# driver_ANNOTATED.net
KiCad netlist of a schematic drawn in EAGLE
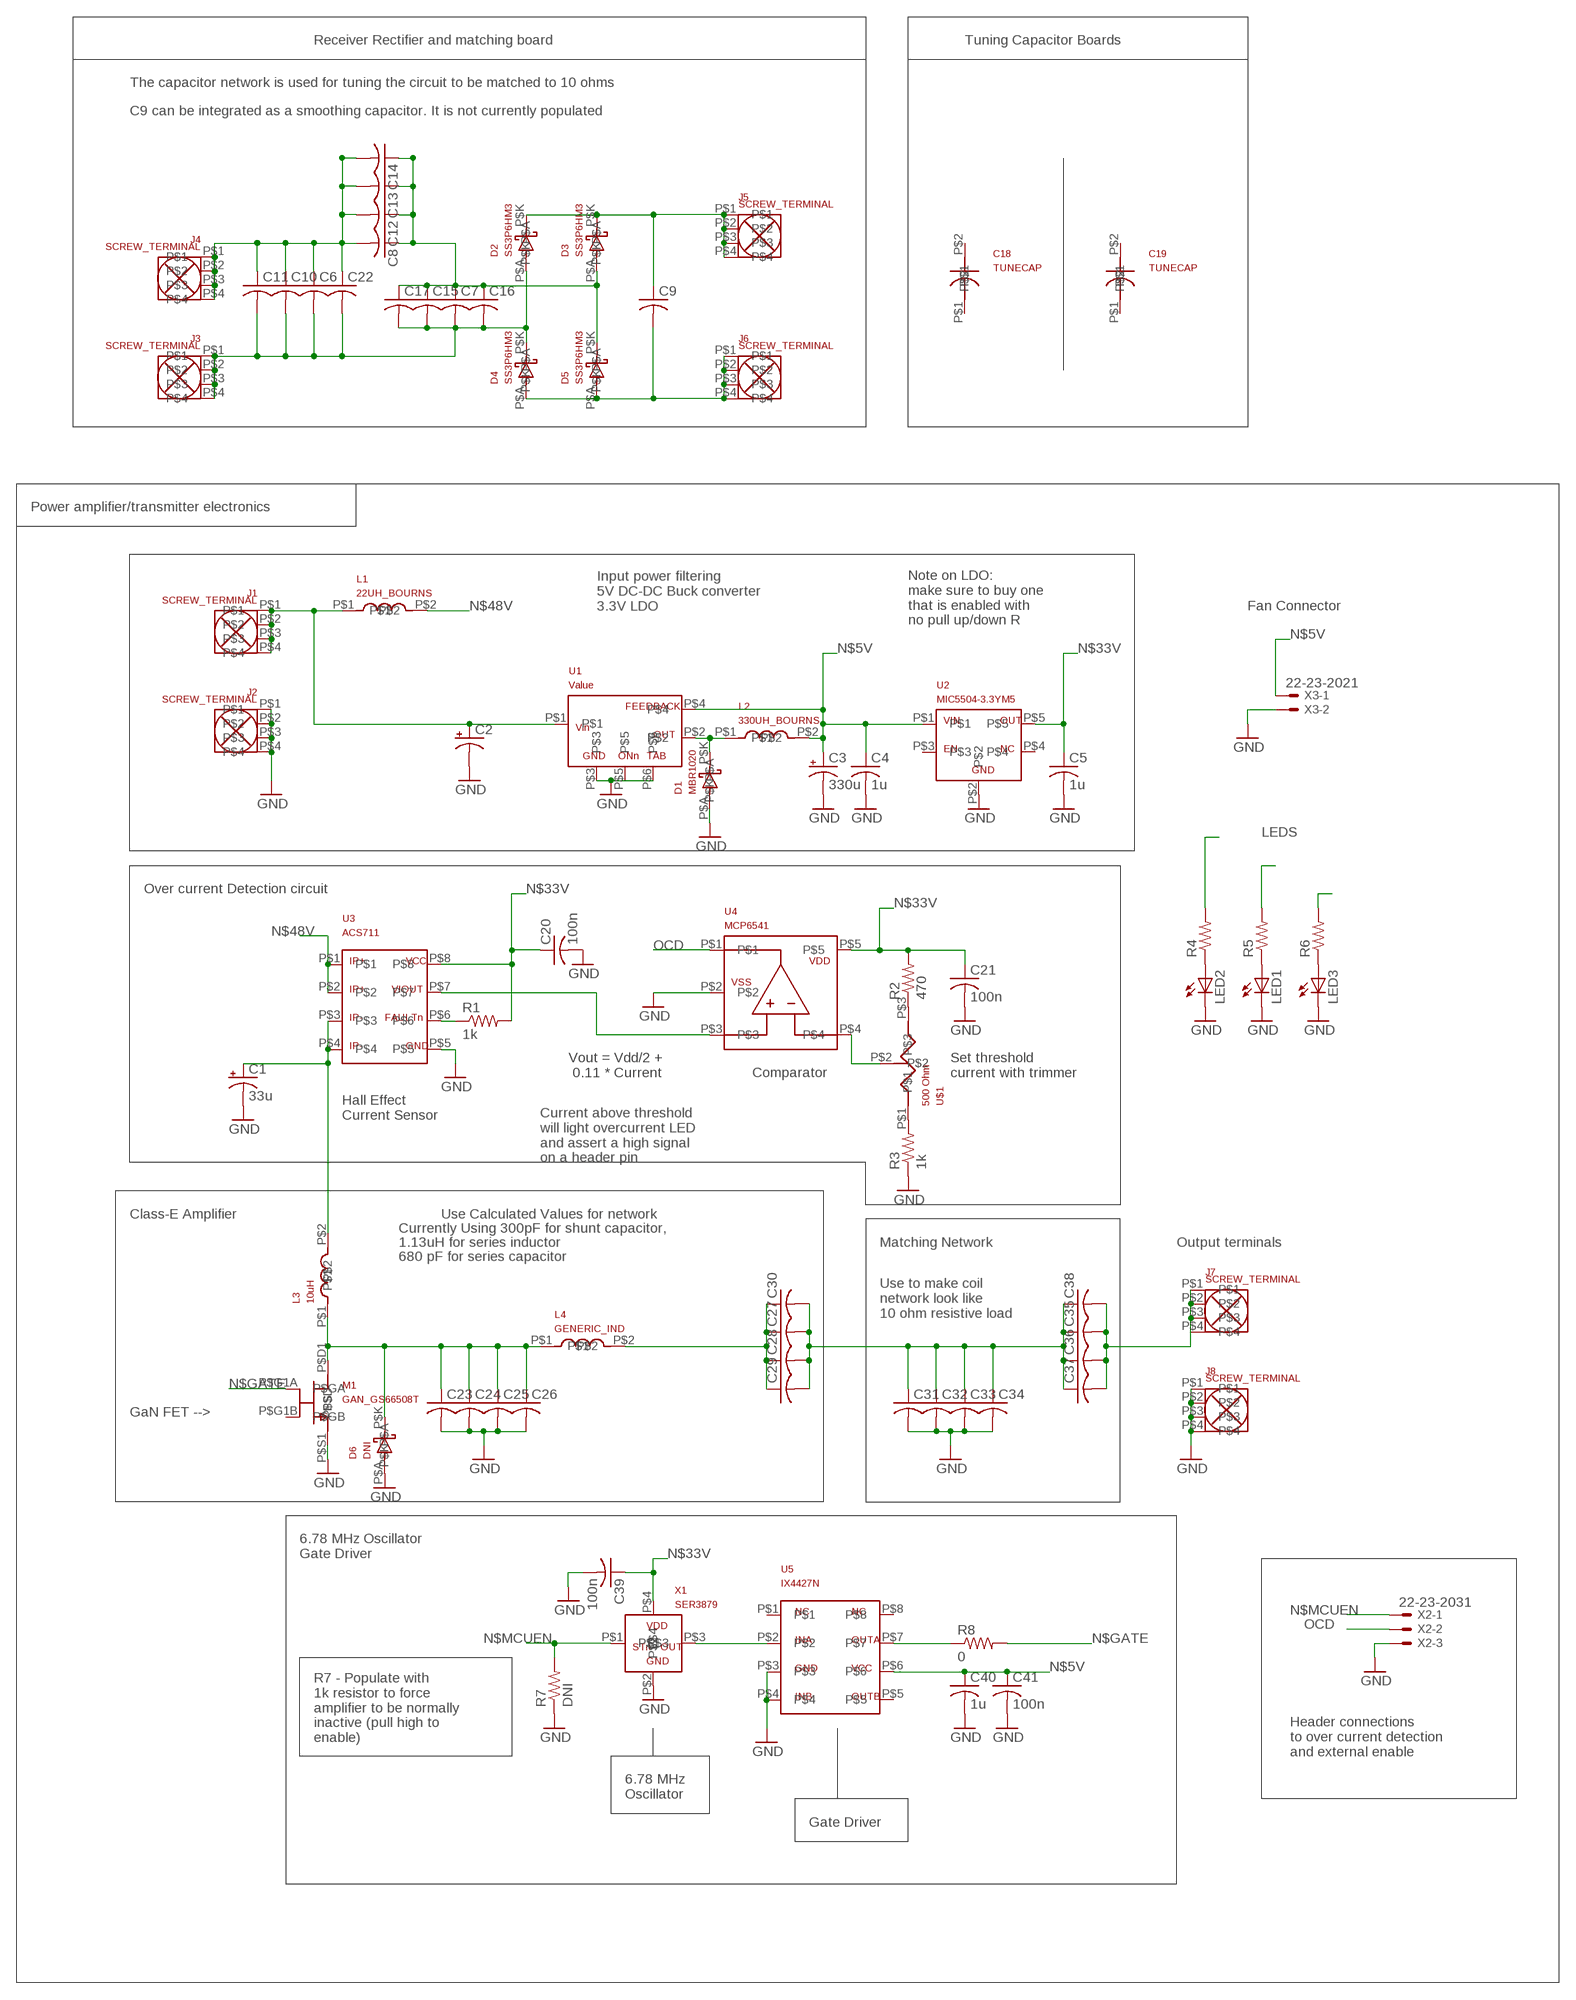
[diagram p0: schematic, sheet 1]

(export (version "E")
  (design (tool "Eeschema 10.0.6"))
  (components
    (comp (ref "C1")
      (value "33u")
      (footprint "eagle-import:140CLH-0810")
      (libsource (lib "eagle-import") (part "CPOL-US140CLH-0810"))
    )
    (comp (ref "C2")
      (value "CPOL-US140CLH-1010")
      (footprint "eagle-import:140CLH-1010")
      (libsource (lib "eagle-import") (part "CPOL-US140CLH-1010"))
    )
    (comp (ref "C3")
      (value "330u")
      (footprint "eagle-import:150CLZ-0810")
      (libsource (lib "eagle-import") (part "CPOL-US150CLZ-0810"))
    )
    (comp (ref "C4")
      (value "1u")
      (footprint "eagle-import:C0603K")
      (libsource (lib "eagle-import") (part "C-USC0603K"))
    )
    (comp (ref "C5")
      (value "1u")
      (footprint "eagle-import:C0603K")
      (libsource (lib "eagle-import") (part "C-USC0603K"))
    )
    (comp (ref "C6")
      (value "C-USC1206K")
      (footprint "eagle-import:C1206K")
      (libsource (lib "eagle-import") (part "C-USC1206K"))
    )
    (comp (ref "C7")
      (value "C-USC1206K")
      (footprint "eagle-import:C1206K")
      (libsource (lib "eagle-import") (part "C-USC1206K"))
    )
    (comp (ref "C8")
      (value "C-USC1206K")
      (footprint "eagle-import:C1206K")
      (libsource (lib "eagle-import") (part "C-USC1206K"))
    )
    (comp (ref "C9")
      (value "C-USC1206K")
      (footprint "eagle-import:C1206K")
      (libsource (lib "eagle-import") (part "C-USC1206K"))
    )
    (comp (ref "C10")
      (value "C-USC1206K")
      (footprint "eagle-import:C1206K")
      (libsource (lib "eagle-import") (part "C-USC1206K"))
    )
    (comp (ref "C11")
      (value "C-USC1206K")
      (footprint "eagle-import:C1206K")
      (libsource (lib "eagle-import") (part "C-USC1206K"))
    )
    (comp (ref "C12")
      (value "C-USC1206K")
      (footprint "eagle-import:C1206K")
      (libsource (lib "eagle-import") (part "C-USC1206K"))
    )
    (comp (ref "C13")
      (value "C-USC1206K")
      (footprint "eagle-import:C1206K")
      (libsource (lib "eagle-import") (part "C-USC1206K"))
    )
    (comp (ref "C14")
      (value "C-USC1206K")
      (footprint "eagle-import:C1206K")
      (libsource (lib "eagle-import") (part "C-USC1206K"))
    )
    (comp (ref "C15")
      (value "C-USC1206K")
      (footprint "eagle-import:C1206K")
      (libsource (lib "eagle-import") (part "C-USC1206K"))
    )
    (comp (ref "C16")
      (value "C-USC1206K")
      (footprint "eagle-import:C1206K")
      (libsource (lib "eagle-import") (part "C-USC1206K"))
    )
    (comp (ref "C17")
      (value "C-USC1206K")
      (footprint "eagle-import:C1206K")
      (libsource (lib "eagle-import") (part "C-USC1206K"))
    )
    (comp (ref "C18")
      (value "TUNECAP")
      (footprint "eagle-import:CAPTUNE")
      (libsource (lib "eagle-import") (part "TUNECAP"))
    )
    (comp (ref "C19")
      (value "TUNECAP")
      (footprint "eagle-import:CAPTUNE")
      (libsource (lib "eagle-import") (part "TUNECAP"))
    )
    (comp (ref "C20")
      (value "100n")
      (footprint "eagle-import:C0603")
      (libsource (lib "eagle-import") (part "C-USC0603"))
    )
    (comp (ref "C21")
      (value "100n")
      (footprint "eagle-import:C0603K")
      (libsource (lib "eagle-import") (part "C-USC0603K"))
    )
    (comp (ref "C22")
      (value "C-USC1206K")
      (footprint "eagle-import:C1206K")
      (libsource (lib "eagle-import") (part "C-USC1206K"))
    )
    (comp (ref "C23")
      (value "C-USC1206K")
      (footprint "eagle-import:C1206K")
      (libsource (lib "eagle-import") (part "C-USC1206K"))
    )
    (comp (ref "C24")
      (value "C-USC1206K")
      (footprint "eagle-import:C1206K")
      (libsource (lib "eagle-import") (part "C-USC1206K"))
    )
    (comp (ref "C25")
      (value "C-USC1206K")
      (footprint "eagle-import:C1206K")
      (libsource (lib "eagle-import") (part "C-USC1206K"))
    )
    (comp (ref "C26")
      (value "C-USC1206K")
      (footprint "eagle-import:C1206K")
      (libsource (lib "eagle-import") (part "C-USC1206K"))
    )
    (comp (ref "C27")
      (value "C-USC1206K")
      (footprint "eagle-import:C1206K")
      (libsource (lib "eagle-import") (part "C-USC1206K"))
    )
    (comp (ref "C28")
      (value "C-USC1206K")
      (footprint "eagle-import:C1206K")
      (libsource (lib "eagle-import") (part "C-USC1206K"))
    )
    (comp (ref "C29")
      (value "C-USC1206K")
      (footprint "eagle-import:C1206K")
      (libsource (lib "eagle-import") (part "C-USC1206K"))
    )
    (comp (ref "C30")
      (value "C-USC1206K")
      (footprint "eagle-import:C1206K")
      (libsource (lib "eagle-import") (part "C-USC1206K"))
    )
    (comp (ref "C31")
      (value "C-USC1206K")
      (footprint "eagle-import:C1206K")
      (libsource (lib "eagle-import") (part "C-USC1206K"))
    )
    (comp (ref "C32")
      (value "C-USC1206K")
      (footprint "eagle-import:C1206K")
      (libsource (lib "eagle-import") (part "C-USC1206K"))
    )
    (comp (ref "C33")
      (value "C-USC1206K")
      (footprint "eagle-import:C1206K")
      (libsource (lib "eagle-import") (part "C-USC1206K"))
    )
    (comp (ref "C34")
      (value "C-USC1206K")
      (footprint "eagle-import:C1206K")
      (libsource (lib "eagle-import") (part "C-USC1206K"))
    )
    (comp (ref "C35")
      (value "C-USC1206K")
      (footprint "eagle-import:C1206K")
      (libsource (lib "eagle-import") (part "C-USC1206K"))
    )
    (comp (ref "C36")
      (value "C-USC1206K")
      (footprint "eagle-import:C1206K")
      (libsource (lib "eagle-import") (part "C-USC1206K"))
    )
    (comp (ref "C37")
      (value "C-USC1206K")
      (footprint "eagle-import:C1206K")
      (libsource (lib "eagle-import") (part "C-USC1206K"))
    )
    (comp (ref "C38")
      (value "C-USC1206K")
      (footprint "eagle-import:C1206K")
      (libsource (lib "eagle-import") (part "C-USC1206K"))
    )
    (comp (ref "C39")
      (value "100n")
      (footprint "eagle-import:C0603K")
      (libsource (lib "eagle-import") (part "C-USC0603K"))
    )
    (comp (ref "C40")
      (value "1u")
      (footprint "eagle-import:C0603K")
      (libsource (lib "eagle-import") (part "C-USC0603K"))
    )
    (comp (ref "C41")
      (value "100n")
      (footprint "eagle-import:C0603K")
      (libsource (lib "eagle-import") (part "C-USC0603K"))
    )
    (comp (ref "D1")
      (value "MBR1020")
      (footprint "eagle-import:SOD-123")
      (libsource (lib "eagle-import") (part "MBR1020"))
    )
    (comp (ref "D2")
      (value "SS3P6HM3")
      (footprint "eagle-import:D0-220")
      (libsource (lib "eagle-import") (part "SS3P6HM3"))
    )
    (comp (ref "D3")
      (value "SS3P6HM3")
      (footprint "eagle-import:D0-220")
      (libsource (lib "eagle-import") (part "SS3P6HM3"))
    )
    (comp (ref "D4")
      (value "SS3P6HM3")
      (footprint "eagle-import:D0-220")
      (libsource (lib "eagle-import") (part "SS3P6HM3"))
    )
    (comp (ref "D5")
      (value "SS3P6HM3")
      (footprint "eagle-import:D0-220")
      (libsource (lib "eagle-import") (part "SS3P6HM3"))
    )
    (comp (ref "D6")
      (value "DNI")
      (footprint "eagle-import:D0-220")
      (libsource (lib "eagle-import") (part "SS3P6HM3"))
    )
    (comp (ref "J1")
      (value "SCREW_TERMINAL")
      (footprint "eagle-import:SCREW_TERMINAL")
      (libsource (lib "eagle-import") (part "SCREW_TERMINAL"))
    )
    (comp (ref "J2")
      (value "SCREW_TERMINAL")
      (footprint "eagle-import:SCREW_TERMINAL")
      (libsource (lib "eagle-import") (part "SCREW_TERMINAL"))
    )
    (comp (ref "J3")
      (value "SCREW_TERMINAL")
      (footprint "eagle-import:SCREW_TERMINAL")
      (libsource (lib "eagle-import") (part "SCREW_TERMINAL"))
    )
    (comp (ref "J4")
      (value "SCREW_TERMINAL")
      (footprint "eagle-import:SCREW_TERMINAL")
      (libsource (lib "eagle-import") (part "SCREW_TERMINAL"))
    )
    (comp (ref "J5")
      (value "SCREW_TERMINAL")
      (footprint "eagle-import:SCREW_TERMINAL")
      (libsource (lib "eagle-import") (part "SCREW_TERMINAL"))
    )
    (comp (ref "J6")
      (value "SCREW_TERMINAL")
      (footprint "eagle-import:SCREW_TERMINAL")
      (libsource (lib "eagle-import") (part "SCREW_TERMINAL"))
    )
    (comp (ref "J7")
      (value "SCREW_TERMINAL")
      (footprint "eagle-import:SCREW_TERMINAL")
      (libsource (lib "eagle-import") (part "SCREW_TERMINAL"))
    )
    (comp (ref "J8")
      (value "SCREW_TERMINAL")
      (footprint "eagle-import:SCREW_TERMINAL")
      (libsource (lib "eagle-import") (part "SCREW_TERMINAL"))
    )
    (comp (ref "L1")
      (value "22UH_BOURNS")
      (footprint "eagle-import:492MIL_IND")
      (libsource (lib "eagle-import") (part "22UH_BOURNS"))
    )
    (comp (ref "L2")
      (value "330UH_BOURNS")
      (footprint "eagle-import:330U_IND")
      (libsource (lib "eagle-import") (part "330UH_BOURNS"))
    )
    (comp (ref "L3")
      (value "10uH")
      (footprint "eagle-import:GENERIC_IND")
      (libsource (lib "eagle-import") (part "GENERIC_IND"))
    )
    (comp (ref "L4")
      (value "GENERIC_IND")
      (footprint "eagle-import:GENERIC_IND")
      (libsource (lib "eagle-import") (part "GENERIC_IND"))
    )
    (comp (ref "LED1")
      (value "LEDCHIPLED_0805")
      (footprint "eagle-import:CHIPLED_0805")
      (libsource (lib "eagle-import") (part "LEDCHIPLED_0805"))
    )
    (comp (ref "LED2")
      (value "LEDCHIPLED_0805")
      (footprint "eagle-import:CHIPLED_0805")
      (libsource (lib "eagle-import") (part "LEDCHIPLED_0805"))
    )
    (comp (ref "LED3")
      (value "LEDCHIPLED_0805")
      (footprint "eagle-import:CHIPLED_0805")
      (libsource (lib "eagle-import") (part "LEDCHIPLED_0805"))
    )
    (comp (ref "M1")
      (value "GAN_GS66508T")
      (footprint "eagle-import:GAN_GS66508T")
      (libsource (lib "eagle-import") (part "GAN_GS66508T"))
    )
    (comp (ref "R1")
      (value "1k")
      (footprint "eagle-import:R0603")
      (libsource (lib "eagle-import") (part "R-US_R0603"))
    )
    (comp (ref "R2")
      (value "470")
      (footprint "eagle-import:R0603")
      (libsource (lib "eagle-import") (part "R-US_R0603"))
    )
    (comp (ref "R3")
      (value "1k")
      (footprint "eagle-import:R0603")
      (libsource (lib "eagle-import") (part "R-US_R0603"))
    )
    (comp (ref "R4")
      (value "R-US_R0603")
      (footprint "eagle-import:R0603")
      (libsource (lib "eagle-import") (part "R-US_R0603"))
    )
    (comp (ref "R5")
      (value "R-US_R0603")
      (footprint "eagle-import:R0603")
      (libsource (lib "eagle-import") (part "R-US_R0603"))
    )
    (comp (ref "R6")
      (value "R-US_R0603")
      (footprint "eagle-import:R0603")
      (libsource (lib "eagle-import") (part "R-US_R0603"))
    )
    (comp (ref "R7")
      (value "DNI")
      (footprint "eagle-import:R0603")
      (libsource (lib "eagle-import") (part "R-US_R0603"))
    )
    (comp (ref "R8")
      (value "0")
      (footprint "eagle-import:R0603")
      (libsource (lib "eagle-import") (part "R-US_R0603"))
    )
    (comp (ref "U$1")
      (value "500 Ohm")
      (footprint "eagle-import:TRIMMER")
      (libsource (lib "eagle-import") (part "TRIMMER"))
    )
    (comp (ref "U1")
      (value "TL2575HV")
      (footprint "eagle-import:TL2575HV")
      (libsource (lib "eagle-import") (part "TL2575HV"))
    )
    (comp (ref "U2")
      (value "MIC5504-3.3YM5")
      (footprint "eagle-import:MIC5504-3.3YM5")
      (libsource (lib "eagle-import") (part "MIC5504-3.3YM5"))
    )
    (comp (ref "U3")
      (value "ACS711")
      (footprint "eagle-import:IX4427N")
      (libsource (lib "eagle-import") (part "ACS711"))
    )
    (comp (ref "U4")
      (value "MCP6541")
      (footprint "eagle-import:SC-70-5")
      (libsource (lib "eagle-import") (part "MCP6541"))
    )
    (comp (ref "U5")
      (value "IX4427N")
      (footprint "eagle-import:IX4427N")
      (libsource (lib "eagle-import") (part "IX4427N"))
    )
    (comp (ref "X1")
      (value "SER3879")
      (footprint "eagle-import:SER3879-ND")
      (libsource (lib "eagle-import") (part "SER3879"))
    )
    (comp (ref "X2")
      (value "22-23-2031")
      (footprint "eagle-import:22-23-2031")
      (fields (field (name "MF") "MOLEX"))
      (libsource (lib "eagle-import") (part "22-23-2031"))
    )
    (comp (ref "X3")
      (value "22-23-2021")
      (footprint "eagle-import:22-23-2021")
      (fields (field (name "MF") "MOLEX"))
      (libsource (lib "eagle-import") (part "22-23-2021"))
    )
  )
  (nets
    (net (code "1") (name "/N$5V") (class "Default")
      (node (ref "C3") (pin "+") (pinfunction "+_+") (pintype "passive"))
      (node (ref "C4") (pin "1") (pinfunction "1_1") (pintype "passive"))
      (node (ref "C40") (pin "1") (pinfunction "1_1") (pintype "passive"))
      (node (ref "C41") (pin "1") (pinfunction "1_1") (pintype "passive"))
      (node (ref "L2") (pin "P$2") (pinfunction "P$2_P$2") (pintype "bidirectional"))
      (node (ref "R4") (pin "2") (pinfunction "2_2") (pintype "passive"))
      (node (ref "U1") (pin "P$4") (pinfunction "P$4_P$4") (pintype "bidirectional"))
      (node (ref "U2") (pin "P$1") (pinfunction "P$1_P$1") (pintype "bidirectional"))
      (node (ref "U5") (pin "P$6") (pinfunction "P$6_P$6") (pintype "bidirectional"))
      (node (ref "X3") (pin "1") (pinfunction "S_1") (pintype "passive"))
    )
    (net (code "2") (name "/N$33V") (class "Default")
      (node (ref "C20") (pin "1") (pinfunction "1_1") (pintype "passive"))
      (node (ref "C21") (pin "1") (pinfunction "1_1") (pintype "passive"))
      (node (ref "C39") (pin "1") (pinfunction "1_1") (pintype "passive"))
      (node (ref "C5") (pin "1") (pinfunction "1_1") (pintype "passive"))
      (node (ref "R1") (pin "2") (pinfunction "2_2") (pintype "passive"))
      (node (ref "R2") (pin "2") (pinfunction "2_2") (pintype "passive"))
      (node (ref "U2") (pin "P$5") (pinfunction "P$5_P$5") (pintype "bidirectional"))
      (node (ref "U3") (pin "P$8") (pinfunction "P$8_P$8") (pintype "bidirectional"))
      (node (ref "U4") (pin "P$5") (pinfunction "P$5_P$5") (pintype "bidirectional"))
      (node (ref "X1") (pin "P$4") (pinfunction "P$4_P$4") (pintype "bidirectional"))
    )
    (net (code "3") (name "/N$48V") (class "Default")
      (node (ref "L1") (pin "P$2") (pinfunction "P$2_P$2") (pintype "bidirectional"))
      (node (ref "U3") (pin "P$1") (pinfunction "P$1_P$1") (pintype "bidirectional"))
      (node (ref "U3") (pin "P$2") (pinfunction "P$2_P$2") (pintype "bidirectional"))
    )
    (net (code "4") (name "/N$GATE") (class "Default")
      (node (ref "M1") (pin "P$G1A") (pinfunction "P$GA_P$G1A") (pintype "bidirectional"))
      (node (ref "R8") (pin "2") (pinfunction "2_2") (pintype "passive"))
    )
    (net (code "5") (name "/N$MCUEN") (class "Default")
      (node (ref "R6") (pin "2") (pinfunction "2_2") (pintype "passive"))
      (node (ref "R7") (pin "2") (pinfunction "2_2") (pintype "passive"))
      (node (ref "X1") (pin "P$1") (pinfunction "P$1_P$1") (pintype "bidirectional"))
      (node (ref "X2") (pin "1") (pinfunction "S_1") (pintype "passive"))
    )
    (net (code "6") (name "/OCD") (class "Default")
      (node (ref "R5") (pin "2") (pinfunction "2_2") (pintype "passive"))
      (node (ref "U4") (pin "P$1") (pinfunction "P$1_P$1") (pintype "bidirectional"))
      (node (ref "X2") (pin "2") (pinfunction "S_2") (pintype "passive"))
    )
    (net (code "7") (name "GND") (class "Default")
      (node (ref "C1") (pin "-") (pinfunction "-_-") (pintype "passive"))
      (node (ref "C2") (pin "-") (pinfunction "-_-") (pintype "passive"))
      (node (ref "C20") (pin "2") (pinfunction "2_2") (pintype "passive"))
      (node (ref "C21") (pin "2") (pinfunction "2_2") (pintype "passive"))
      (node (ref "C23") (pin "2") (pinfunction "2_2") (pintype "passive"))
      (node (ref "C24") (pin "2") (pinfunction "2_2") (pintype "passive"))
      (node (ref "C25") (pin "2") (pinfunction "2_2") (pintype "passive"))
      (node (ref "C26") (pin "2") (pinfunction "2_2") (pintype "passive"))
      (node (ref "C3") (pin "-") (pinfunction "-_-") (pintype "passive"))
      (node (ref "C31") (pin "2") (pinfunction "2_2") (pintype "passive"))
      (node (ref "C32") (pin "2") (pinfunction "2_2") (pintype "passive"))
      (node (ref "C33") (pin "2") (pinfunction "2_2") (pintype "passive"))
      (node (ref "C34") (pin "2") (pinfunction "2_2") (pintype "passive"))
      (node (ref "C39") (pin "2") (pinfunction "2_2") (pintype "passive"))
      (node (ref "C4") (pin "2") (pinfunction "2_2") (pintype "passive"))
      (node (ref "C40") (pin "2") (pinfunction "2_2") (pintype "passive"))
      (node (ref "C41") (pin "2") (pinfunction "2_2") (pintype "passive"))
      (node (ref "C5") (pin "2") (pinfunction "2_2") (pintype "passive"))
      (node (ref "D1") (pin "P$A") (pinfunction "P$A_P$A") (pintype "bidirectional"))
      (node (ref "D6") (pin "P$A") (pinfunction "P$A_P$A") (pintype "bidirectional"))
      (node (ref "J2") (pin "P$1") (pinfunction "P$1_P$1") (pintype "bidirectional"))
      (node (ref "J2") (pin "P$2") (pinfunction "P$2_P$2") (pintype "bidirectional"))
      (node (ref "J2") (pin "P$3") (pinfunction "P$3_P$3") (pintype "bidirectional"))
      (node (ref "J2") (pin "P$4") (pinfunction "P$4_P$4") (pintype "bidirectional"))
      (node (ref "J8") (pin "P$1") (pinfunction "P$1_P$1") (pintype "bidirectional"))
      (node (ref "J8") (pin "P$2") (pinfunction "P$2_P$2") (pintype "bidirectional"))
      (node (ref "J8") (pin "P$3") (pinfunction "P$3_P$3") (pintype "bidirectional"))
      (node (ref "J8") (pin "P$4") (pinfunction "P$4_P$4") (pintype "bidirectional"))
      (node (ref "LED1") (pin "C") (pinfunction "C_C") (pintype "passive"))
      (node (ref "LED2") (pin "C") (pinfunction "C_C") (pintype "passive"))
      (node (ref "LED3") (pin "C") (pinfunction "C_C") (pintype "passive"))
      (node (ref "M1") (pin "P$S1") (pinfunction "P$S_P$S1") (pintype "bidirectional"))
      (node (ref "R3") (pin "1") (pinfunction "1_1") (pintype "passive"))
      (node (ref "R7") (pin "1") (pinfunction "1_1") (pintype "passive"))
      (node (ref "U1") (pin "P$3") (pinfunction "P$3_P$3") (pintype "bidirectional"))
      (node (ref "U1") (pin "P$5") (pinfunction "P$5_P$5") (pintype "bidirectional"))
      (node (ref "U1") (pin "P$6") (pinfunction "P$6_P$6") (pintype "bidirectional"))
      (node (ref "U2") (pin "P$2") (pinfunction "P$2_P$2") (pintype "bidirectional"))
      (node (ref "U3") (pin "P$5") (pinfunction "P$5_P$5") (pintype "bidirectional"))
      (node (ref "U4") (pin "P$2") (pinfunction "P$2_P$2") (pintype "bidirectional"))
      (node (ref "U5") (pin "P$3") (pinfunction "P$3_P$3") (pintype "bidirectional"))
      (node (ref "U5") (pin "P$4") (pinfunction "P$4_P$4") (pintype "bidirectional"))
      (node (ref "X1") (pin "P$2") (pinfunction "P$2_P$2") (pintype "bidirectional"))
      (node (ref "X2") (pin "3") (pinfunction "S_3") (pintype "passive"))
      (node (ref "X3") (pin "2") (pinfunction "S_2") (pintype "passive"))
    )
    (net (code "8") (name "Net-(C1-Pad+)") (class "Default")
      (node (ref "C1") (pin "+") (pinfunction "+_+") (pintype "passive"))
      (node (ref "L3") (pin "P$2") (pinfunction "P$2_P$2") (pintype "bidirectional"))
      (node (ref "U3") (pin "P$3") (pinfunction "P$3_P$3") (pintype "bidirectional"))
      (node (ref "U3") (pin "P$4") (pinfunction "P$4_P$4") (pintype "bidirectional"))
    )
    (net (code "9") (name "Net-(C2-Pad+)") (class "Default")
      (node (ref "C2") (pin "+") (pinfunction "+_+") (pintype "passive"))
      (node (ref "J1") (pin "P$1") (pinfunction "P$1_P$1") (pintype "bidirectional"))
      (node (ref "J1") (pin "P$2") (pinfunction "P$2_P$2") (pintype "bidirectional"))
      (node (ref "J1") (pin "P$3") (pinfunction "P$3_P$3") (pintype "bidirectional"))
      (node (ref "J1") (pin "P$4") (pinfunction "P$4_P$4") (pintype "bidirectional"))
      (node (ref "L1") (pin "P$1") (pinfunction "P$1_P$1") (pintype "bidirectional"))
      (node (ref "U1") (pin "P$1") (pinfunction "P$1_P$1") (pintype "bidirectional"))
    )
    (net (code "10") (name "Net-(C9-Pad1)") (class "Default")
      (node (ref "C9") (pin "1") (pinfunction "1_1") (pintype "passive"))
      (node (ref "D2") (pin "P$K") (pinfunction "P$K_P$K") (pintype "bidirectional"))
      (node (ref "D3") (pin "P$K") (pinfunction "P$K_P$K") (pintype "bidirectional"))
      (node (ref "J5") (pin "P$1") (pinfunction "P$1_P$1") (pintype "bidirectional"))
      (node (ref "J5") (pin "P$2") (pinfunction "P$2_P$2") (pintype "bidirectional"))
      (node (ref "J5") (pin "P$3") (pinfunction "P$3_P$3") (pintype "bidirectional"))
      (node (ref "J5") (pin "P$4") (pinfunction "P$4_P$4") (pintype "bidirectional"))
    )
    (net (code "11") (name "Net-(C9-Pad2)") (class "Default")
      (node (ref "C9") (pin "2") (pinfunction "2_2") (pintype "passive"))
      (node (ref "D4") (pin "P$A") (pinfunction "P$A_P$A") (pintype "bidirectional"))
      (node (ref "D5") (pin "P$A") (pinfunction "P$A_P$A") (pintype "bidirectional"))
      (node (ref "J6") (pin "P$1") (pinfunction "P$1_P$1") (pintype "bidirectional"))
      (node (ref "J6") (pin "P$2") (pinfunction "P$2_P$2") (pintype "bidirectional"))
      (node (ref "J6") (pin "P$3") (pinfunction "P$3_P$3") (pintype "bidirectional"))
      (node (ref "J6") (pin "P$4") (pinfunction "P$4_P$4") (pintype "bidirectional"))
    )
    (net (code "12") (name "Net-(C10-Pad1)") (class "Default")
      (node (ref "C10") (pin "1") (pinfunction "1_1") (pintype "passive"))
      (node (ref "C11") (pin "1") (pinfunction "1_1") (pintype "passive"))
      (node (ref "C12") (pin "2") (pinfunction "2_2") (pintype "passive"))
      (node (ref "C13") (pin "2") (pinfunction "2_2") (pintype "passive"))
      (node (ref "C14") (pin "2") (pinfunction "2_2") (pintype "passive"))
      (node (ref "C22") (pin "1") (pinfunction "1_1") (pintype "passive"))
      (node (ref "C6") (pin "1") (pinfunction "1_1") (pintype "passive"))
      (node (ref "C8") (pin "2") (pinfunction "2_2") (pintype "passive"))
      (node (ref "J4") (pin "P$1") (pinfunction "P$1_P$1") (pintype "bidirectional"))
      (node (ref "J4") (pin "P$2") (pinfunction "P$2_P$2") (pintype "bidirectional"))
      (node (ref "J4") (pin "P$3") (pinfunction "P$3_P$3") (pintype "bidirectional"))
      (node (ref "J4") (pin "P$4") (pinfunction "P$4_P$4") (pintype "bidirectional"))
    )
    (net (code "13") (name "Net-(C10-Pad2)") (class "Default")
      (node (ref "C10") (pin "2") (pinfunction "2_2") (pintype "passive"))
      (node (ref "C11") (pin "2") (pinfunction "2_2") (pintype "passive"))
      (node (ref "C15") (pin "2") (pinfunction "2_2") (pintype "passive"))
      (node (ref "C16") (pin "2") (pinfunction "2_2") (pintype "passive"))
      (node (ref "C17") (pin "2") (pinfunction "2_2") (pintype "passive"))
      (node (ref "C22") (pin "2") (pinfunction "2_2") (pintype "passive"))
      (node (ref "C6") (pin "2") (pinfunction "2_2") (pintype "passive"))
      (node (ref "C7") (pin "2") (pinfunction "2_2") (pintype "passive"))
      (node (ref "D2") (pin "P$A") (pinfunction "P$A_P$A") (pintype "bidirectional"))
      (node (ref "D4") (pin "P$K") (pinfunction "P$K_P$K") (pintype "bidirectional"))
      (node (ref "J3") (pin "P$1") (pinfunction "P$1_P$1") (pintype "bidirectional"))
      (node (ref "J3") (pin "P$2") (pinfunction "P$2_P$2") (pintype "bidirectional"))
      (node (ref "J3") (pin "P$3") (pinfunction "P$3_P$3") (pintype "bidirectional"))
      (node (ref "J3") (pin "P$4") (pinfunction "P$4_P$4") (pintype "bidirectional"))
    )
    (net (code "14") (name "Net-(C12-Pad1)") (class "Default")
      (node (ref "C12") (pin "1") (pinfunction "1_1") (pintype "passive"))
      (node (ref "C13") (pin "1") (pinfunction "1_1") (pintype "passive"))
      (node (ref "C14") (pin "1") (pinfunction "1_1") (pintype "passive"))
      (node (ref "C15") (pin "1") (pinfunction "1_1") (pintype "passive"))
      (node (ref "C16") (pin "1") (pinfunction "1_1") (pintype "passive"))
      (node (ref "C17") (pin "1") (pinfunction "1_1") (pintype "passive"))
      (node (ref "C7") (pin "1") (pinfunction "1_1") (pintype "passive"))
      (node (ref "C8") (pin "1") (pinfunction "1_1") (pintype "passive"))
      (node (ref "D3") (pin "P$A") (pinfunction "P$A_P$A") (pintype "bidirectional"))
      (node (ref "D5") (pin "P$K") (pinfunction "P$K_P$K") (pintype "bidirectional"))
    )
    (net (code "15") (name "Net-(C27-Pad1)") (class "Default")
      (node (ref "C27") (pin "1") (pinfunction "1_1") (pintype "passive"))
      (node (ref "C28") (pin "1") (pinfunction "1_1") (pintype "passive"))
      (node (ref "C29") (pin "1") (pinfunction "1_1") (pintype "passive"))
      (node (ref "C30") (pin "1") (pinfunction "1_1") (pintype "passive"))
      (node (ref "L4") (pin "P$2") (pinfunction "P$2_P$2") (pintype "bidirectional"))
    )
    (net (code "16") (name "Net-(C27-Pad2)") (class "Default")
      (node (ref "C27") (pin "2") (pinfunction "2_2") (pintype "passive"))
      (node (ref "C28") (pin "2") (pinfunction "2_2") (pintype "passive"))
      (node (ref "C29") (pin "2") (pinfunction "2_2") (pintype "passive"))
      (node (ref "C30") (pin "2") (pinfunction "2_2") (pintype "passive"))
      (node (ref "C31") (pin "1") (pinfunction "1_1") (pintype "passive"))
      (node (ref "C32") (pin "1") (pinfunction "1_1") (pintype "passive"))
      (node (ref "C33") (pin "1") (pinfunction "1_1") (pintype "passive"))
      (node (ref "C34") (pin "1") (pinfunction "1_1") (pintype "passive"))
      (node (ref "C35") (pin "1") (pinfunction "1_1") (pintype "passive"))
      (node (ref "C36") (pin "1") (pinfunction "1_1") (pintype "passive"))
      (node (ref "C37") (pin "1") (pinfunction "1_1") (pintype "passive"))
      (node (ref "C38") (pin "1") (pinfunction "1_1") (pintype "passive"))
    )
    (net (code "17") (name "Net-(C35-Pad2)") (class "Default")
      (node (ref "C35") (pin "2") (pinfunction "2_2") (pintype "passive"))
      (node (ref "C36") (pin "2") (pinfunction "2_2") (pintype "passive"))
      (node (ref "C37") (pin "2") (pinfunction "2_2") (pintype "passive"))
      (node (ref "C38") (pin "2") (pinfunction "2_2") (pintype "passive"))
      (node (ref "J7") (pin "P$1") (pinfunction "P$1_P$1") (pintype "bidirectional"))
      (node (ref "J7") (pin "P$2") (pinfunction "P$2_P$2") (pintype "bidirectional"))
      (node (ref "J7") (pin "P$3") (pinfunction "P$3_P$3") (pintype "bidirectional"))
      (node (ref "J7") (pin "P$4") (pinfunction "P$4_P$4") (pintype "bidirectional"))
    )
    (net (code "18") (name "Net-(D1-PadP$K)") (class "Default")
      (node (ref "D1") (pin "P$K") (pinfunction "P$K_P$K") (pintype "bidirectional"))
      (node (ref "L2") (pin "P$1") (pinfunction "P$1_P$1") (pintype "bidirectional"))
      (node (ref "U1") (pin "P$2") (pinfunction "P$2_P$2") (pintype "bidirectional"))
    )
    (net (code "19") (name "Net-(LED1-PadA)") (class "Default")
      (node (ref "LED1") (pin "A") (pinfunction "A_A") (pintype "passive"))
      (node (ref "R5") (pin "1") (pinfunction "1_1") (pintype "passive"))
    )
    (net (code "20") (name "Net-(LED2-PadA)") (class "Default")
      (node (ref "LED2") (pin "A") (pinfunction "A_A") (pintype "passive"))
      (node (ref "R4") (pin "1") (pinfunction "1_1") (pintype "passive"))
    )
    (net (code "21") (name "Net-(LED3-PadA)") (class "Default")
      (node (ref "LED3") (pin "A") (pinfunction "A_A") (pintype "passive"))
      (node (ref "R6") (pin "1") (pinfunction "1_1") (pintype "passive"))
    )
    (net (code "22") (name "Net-(M1-P$D)") (class "Default")
      (node (ref "C23") (pin "1") (pinfunction "1_1") (pintype "passive"))
      (node (ref "C24") (pin "1") (pinfunction "1_1") (pintype "passive"))
      (node (ref "C25") (pin "1") (pinfunction "1_1") (pintype "passive"))
      (node (ref "C26") (pin "1") (pinfunction "1_1") (pintype "passive"))
      (node (ref "D6") (pin "P$K") (pinfunction "P$K_P$K") (pintype "bidirectional"))
      (node (ref "L3") (pin "P$1") (pinfunction "P$1_P$1") (pintype "bidirectional"))
      (node (ref "L4") (pin "P$1") (pinfunction "P$1_P$1") (pintype "bidirectional"))
      (node (ref "M1") (pin "P$D1") (pinfunction "P$D_P$D1") (pintype "bidirectional"))
    )
    (net (code "23") (name "Net-(R1-Pad1)") (class "Default")
      (node (ref "R1") (pin "1") (pinfunction "1_1") (pintype "passive"))
      (node (ref "U3") (pin "P$6") (pinfunction "P$6_P$6") (pintype "bidirectional"))
    )
    (net (code "24") (name "Net-(R2-Pad1)") (class "Default")
      (node (ref "R2") (pin "1") (pinfunction "1_1") (pintype "passive"))
      (node (ref "U$1") (pin "P$3") (pinfunction "P$3_P$3") (pintype "bidirectional"))
    )
    (net (code "25") (name "Net-(R3-Pad2)") (class "Default")
      (node (ref "R3") (pin "2") (pinfunction "2_2") (pintype "passive"))
      (node (ref "U$1") (pin "P$1") (pinfunction "P$1_P$1") (pintype "bidirectional"))
    )
    (net (code "26") (name "Net-(R8-Pad1)") (class "Default")
      (node (ref "R8") (pin "1") (pinfunction "1_1") (pintype "passive"))
      (node (ref "U5") (pin "P$7") (pinfunction "P$7_P$7") (pintype "bidirectional"))
    )
    (net (code "27") (name "Net-(U$1-PadP$2)") (class "Default")
      (node (ref "U$1") (pin "P$2") (pinfunction "P$2_P$2") (pintype "bidirectional"))
      (node (ref "U4") (pin "P$4") (pinfunction "P$4_P$4") (pintype "bidirectional"))
    )
    (net (code "28") (name "Net-(U3-PadP$7)") (class "Default")
      (node (ref "U3") (pin "P$7") (pinfunction "P$7_P$7") (pintype "bidirectional"))
      (node (ref "U4") (pin "P$3") (pinfunction "P$3_P$3") (pintype "bidirectional"))
    )
    (net (code "29") (name "Net-(U5-PadP$2)") (class "Default")
      (node (ref "U5") (pin "P$2") (pinfunction "P$2_P$2") (pintype "bidirectional"))
      (node (ref "X1") (pin "P$3") (pinfunction "P$3_P$3") (pintype "bidirectional"))
    )
    (net (code "30") (name "unconnected-(C18-PadP$1)") (class "Default")
      (node (ref "C18") (pin "P$1") (pinfunction "P$1_P$1") (pintype "bidirectional"))
    )
    (net (code "31") (name "unconnected-(C18-PadP$2)") (class "Default")
      (node (ref "C18") (pin "P$2") (pinfunction "P$2_P$2") (pintype "bidirectional"))
    )
    (net (code "32") (name "unconnected-(C19-PadP$1)") (class "Default")
      (node (ref "C19") (pin "P$1") (pinfunction "P$1_P$1") (pintype "bidirectional"))
    )
    (net (code "33") (name "unconnected-(C19-PadP$2)") (class "Default")
      (node (ref "C19") (pin "P$2") (pinfunction "P$2_P$2") (pintype "bidirectional"))
    )
    (net (code "34") (name "unconnected-(M1-P$GB-PadP$G1B)") (class "Default")
      (node (ref "M1") (pin "P$G1B") (pinfunction "P$GB_P$G1B") (pintype "bidirectional"))
    )
    (net (code "35") (name "unconnected-(U2-PadP$3)") (class "Default")
      (node (ref "U2") (pin "P$3") (pinfunction "P$3_P$3") (pintype "bidirectional"))
    )
    (net (code "36") (name "unconnected-(U2-PadP$4)") (class "Default")
      (node (ref "U2") (pin "P$4") (pinfunction "P$4_P$4") (pintype "bidirectional"))
    )
    (net (code "37") (name "unconnected-(U5-PadP$1)") (class "Default")
      (node (ref "U5") (pin "P$1") (pinfunction "P$1_P$1") (pintype "bidirectional"))
    )
    (net (code "38") (name "unconnected-(U5-PadP$5)") (class "Default")
      (node (ref "U5") (pin "P$5") (pinfunction "P$5_P$5") (pintype "bidirectional"))
    )
    (net (code "39") (name "unconnected-(U5-PadP$8)") (class "Default")
      (node (ref "U5") (pin "P$8") (pinfunction "P$8_P$8") (pintype "bidirectional"))
    )
  )
)
